# ExtendMain.net
KiCad netlist of a schematic drawn in Altium Designer
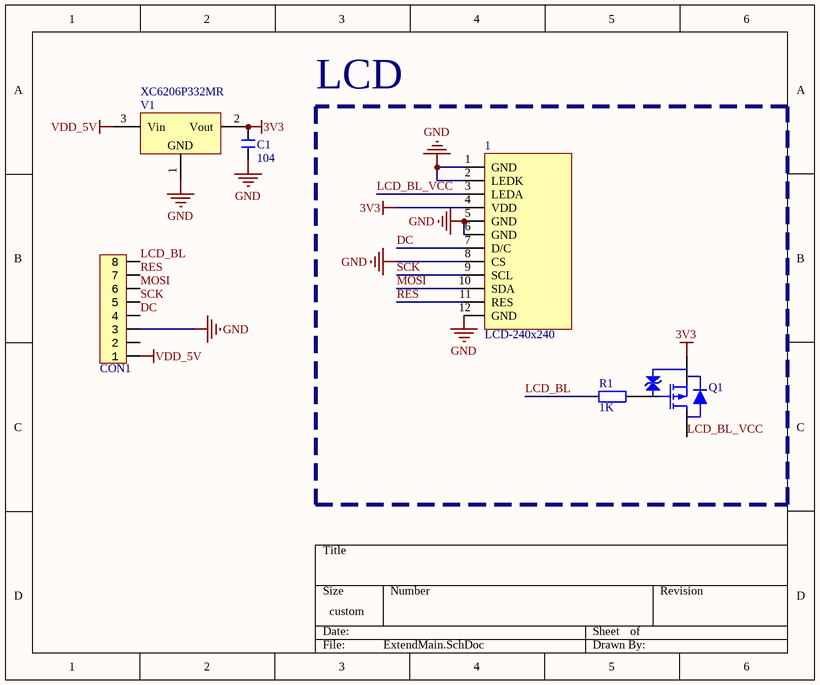
[diagram p0: ExtendMain.SchDoc]

(export (version "E")
  (design (tool "Eeschema 10.0.6"))
  (components
    (comp (ref "1")
      (value "LCD-240x240")
      (footprint "LCD-240x240-NoHole")
      (description "显示屏")
      (libsource (lib "mLib") (part "LCD-240x240"))
    )
    (comp (ref "C1")
      (value "104")
      (footprint "C 0402_M")
      (description "无极性贴片电容")
      (libsource (lib "ExtendBoard_1") (part "C"))
    )
    (comp (ref "CON1")
      (value "FFC_0.5_8")
      (footprint "FFC_0.5_8")
      (description "FFC")
      (libsource (lib "KitSprout") (part "FFC_0.5_8"))
    )
    (comp (ref "Q1")
      (value "AO3415A")
      (footprint "SOT23-3")
      (description "MOSFET")
      (fields (field (name "PUBLISHER") "Altium Limited"))
      (libsource (lib "MyPcbLib") (part "AO3415A"))
    )
    (comp (ref "R1")
      (value "1K")
      (footprint "RES_0402")
      (description "Resistor")
      (libsource (lib "MyPcbLib") (part "电阻-0402"))
    )
    (comp (ref "V1")
      (value "XC6206P332MR")
      (footprint "SOT23-3L")
      (description "低压差线性稳压芯片")
      (libsource (lib "ExtendBoard_1") (part "XC6206P332MR"))
    )
  )
  (nets
    (net (code "1") (name "/DC") (class "Default")
      (node (ref "1") (pin "7") (pinfunction "D/C_7") (pintype "passive"))
      (node (ref "CON1") (pin "4") (pinfunction "4_4") (pintype "passive"))
    )
    (net (code "2") (name "/LCD_BL") (class "Default")
      (node (ref "CON1") (pin "8") (pinfunction "8_8") (pintype "passive"))
      (node (ref "R1") (pin "1") (pinfunction "1_1") (pintype "passive"))
    )
    (net (code "3") (name "/LCD_BL_VCC") (class "Default")
      (node (ref "1") (pin "3") (pinfunction "LEDA_3") (pintype "passive"))
      (node (ref "Q1") (pin "3") (pinfunction "D_3") (pintype "passive"))
    )
    (net (code "4") (name "/MOSI") (class "Default")
      (node (ref "1") (pin "10") (pinfunction "SDA_10") (pintype "passive"))
      (node (ref "CON1") (pin "6") (pinfunction "6_6") (pintype "passive"))
    )
    (net (code "5") (name "/RES") (class "Default")
      (node (ref "1") (pin "11") (pinfunction "RES_11") (pintype "passive"))
      (node (ref "CON1") (pin "7") (pinfunction "7_7") (pintype "passive"))
    )
    (net (code "6") (name "/SCK") (class "Default")
      (node (ref "1") (pin "9") (pinfunction "SCL_9") (pintype "passive"))
      (node (ref "CON1") (pin "5") (pinfunction "5_5") (pintype "passive"))
    )
    (net (code "7") (name "3V3") (class "Default")
      (node (ref "1") (pin "4") (pinfunction "VDD_4") (pintype "passive"))
      (node (ref "C1") (pin "2") (pinfunction "2_2") (pintype "passive"))
      (node (ref "Q1") (pin "2") (pinfunction "S_2") (pintype "passive"))
      (node (ref "V1") (pin "2") (pinfunction "Vout_2") (pintype "passive"))
    )
    (net (code "8") (name "GND") (class "Default")
      (node (ref "1") (pin "1") (pinfunction "GND_1") (pintype "passive"))
      (node (ref "1") (pin "12") (pinfunction "GND_12") (pintype "passive"))
      (node (ref "1") (pin "2") (pinfunction "LEDK_2") (pintype "passive"))
      (node (ref "1") (pin "5") (pinfunction "GND_5") (pintype "passive"))
      (node (ref "1") (pin "6") (pinfunction "GND_6") (pintype "passive"))
      (node (ref "1") (pin "8") (pinfunction "CS_8") (pintype "passive"))
      (node (ref "C1") (pin "1") (pinfunction "1_1") (pintype "passive"))
      (node (ref "CON1") (pin "3") (pinfunction "3_3") (pintype "passive"))
      (node (ref "V1") (pin "1") (pinfunction "GND_1") (pintype "passive"))
    )
    (net (code "9") (name "Net-(Q1-G)") (class "Default")
      (node (ref "Q1") (pin "1") (pinfunction "G_1") (pintype "passive"))
      (node (ref "R1") (pin "2") (pinfunction "2_2") (pintype "passive"))
    )
    (net (code "10") (name "VDD_5V") (class "Default")
      (node (ref "CON1") (pin "1") (pinfunction "1_1") (pintype "passive"))
      (node (ref "V1") (pin "3") (pinfunction "Vin_3") (pintype "passive"))
    )
    (net (code "11") (name "unconnected-(CON1-Pad2)") (class "Default")
      (node (ref "CON1") (pin "2") (pinfunction "2_2") (pintype "passive"))
    )
  )
)
